# relayboard-v1.net
KiCad netlist of a schematic drawn in EAGLE
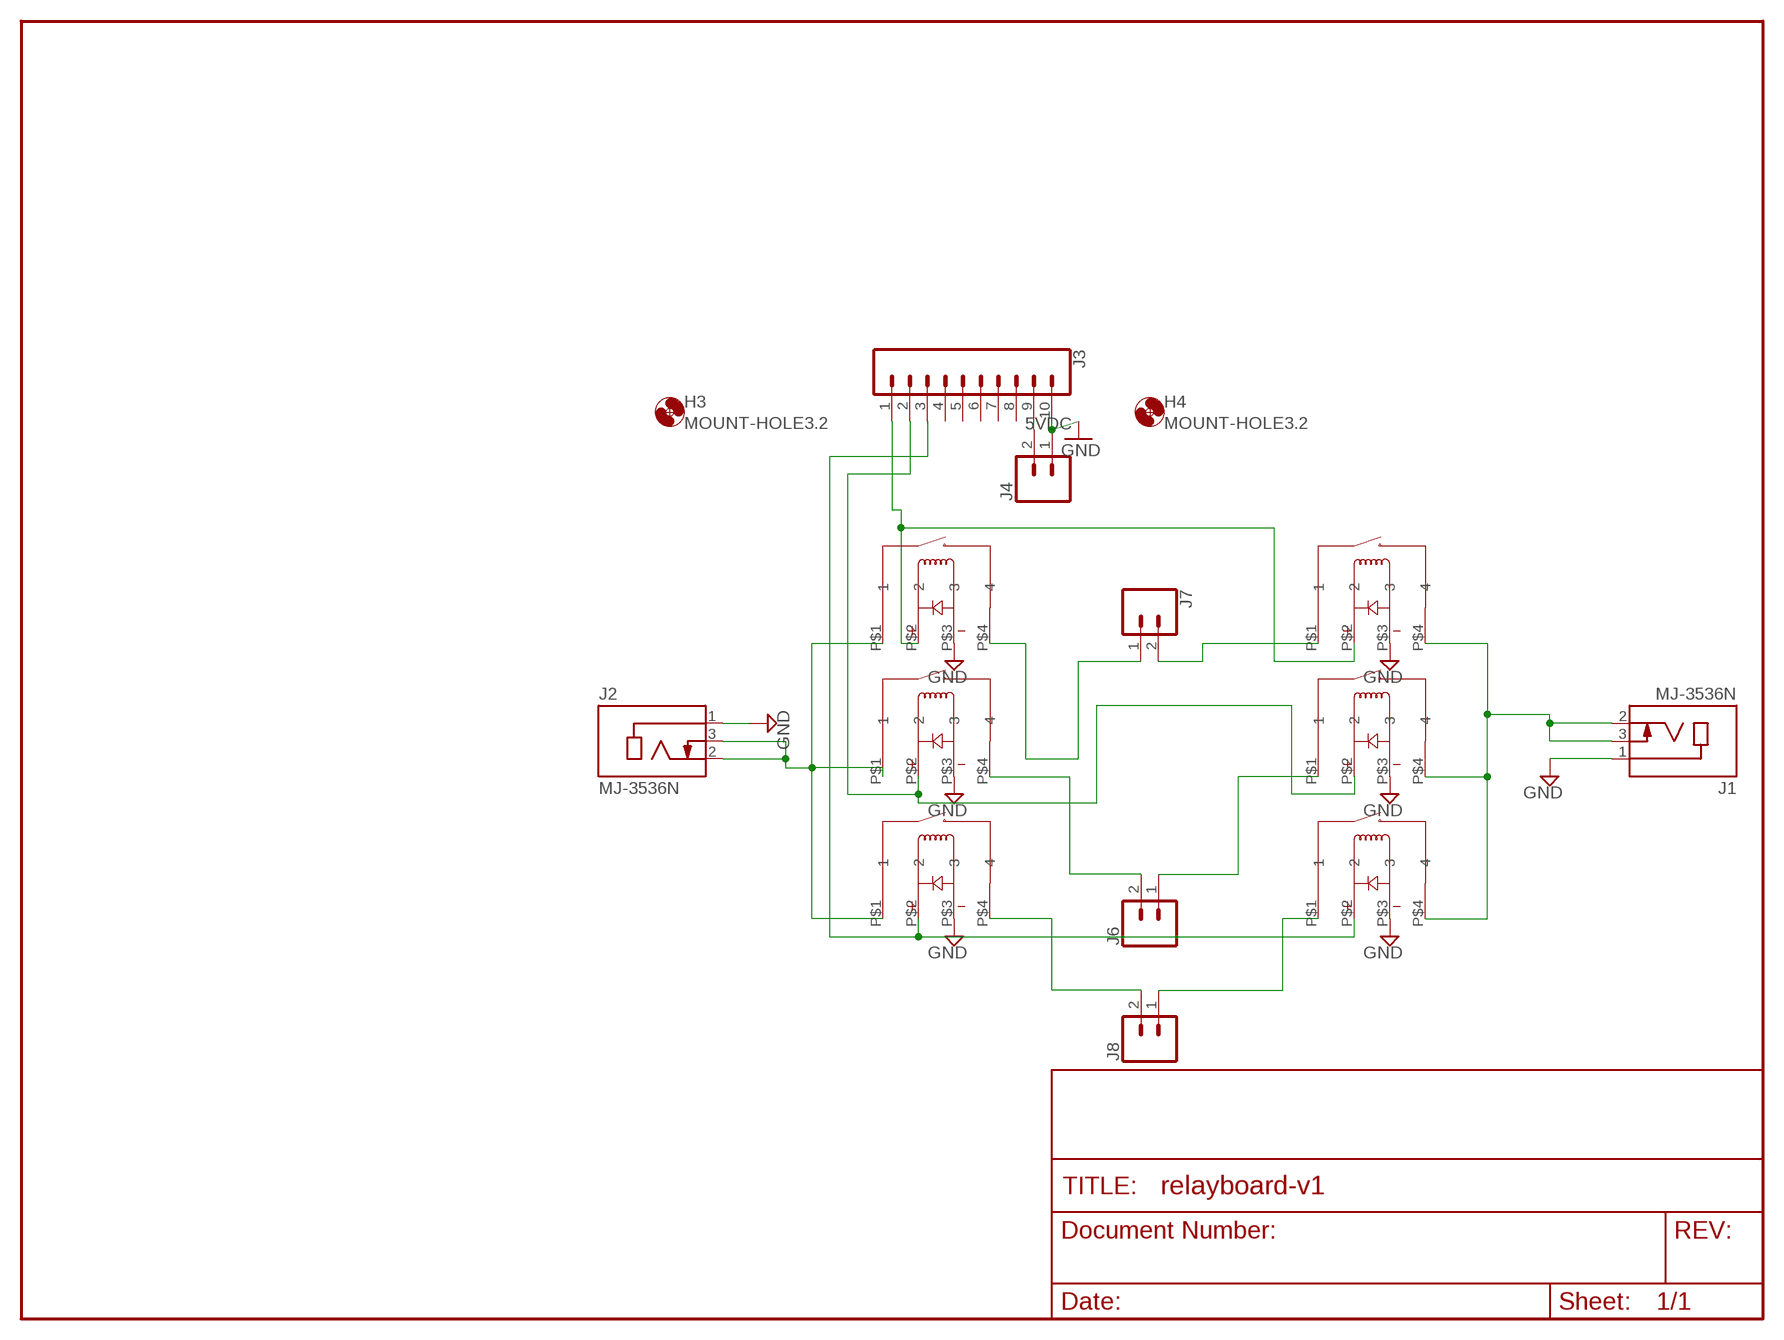
[diagram p0: schematic, sheet 1]

(export (version "E")
  (design (tool "Eeschema 10.0.6"))
  (components
    (comp (ref "H3")
      (value "MOUNT-HOLE3.2")
      (footprint "eagle-import:3,2")
      (libsource (lib "eagle-import") (part "MOUNT-HOLE3.2"))
    )
    (comp (ref "H4")
      (value "MOUNT-HOLE3.2")
      (footprint "eagle-import:3,2")
      (libsource (lib "eagle-import") (part "MOUNT-HOLE3.2"))
    )
    (comp (ref "J1")
      (value "MJ-3536N")
      (footprint "eagle-import:CUI_MJ-3536N")
      (fields (field (name "MANUFACTURER") "CUI INC"))
      (libsource (lib "eagle-import") (part "MJ-3536N"))
    )
    (comp (ref "J2")
      (value "MJ-3536N")
      (footprint "eagle-import:CUI_MJ-3536N")
      (fields (field (name "MANUFACTURER") "CUI INC"))
      (libsource (lib "eagle-import") (part "MJ-3536N"))
    )
    (comp (ref "J3")
      (value "CONN_10\"")
      (footprint "eagle-import:1X10")
      (libsource (lib "eagle-import") (part "CONN_10{dblquote}"))
    )
    (comp (ref "J4")
      (value "CONN_02")
      (footprint "eagle-import:1X02")
      (libsource (lib "eagle-import") (part "CONN_02"))
    )
    (comp (ref "J6")
      (value "CONN_02")
      (footprint "eagle-import:1X02")
      (libsource (lib "eagle-import") (part "CONN_02"))
    )
    (comp (ref "J7")
      (value "CONN_02")
      (footprint "eagle-import:1X02")
      (libsource (lib "eagle-import") (part "CONN_02"))
    )
    (comp (ref "J8")
      (value "CONN_02")
      (footprint "eagle-import:1X02")
      (libsource (lib "eagle-import") (part "CONN_02"))
    )
    (comp (ref "U$3")
      (value "RELAY-COMUS-3750-1331")
      (footprint "eagle-import:RELAY-COMUS-3570-1331")
      (libsource (lib "eagle-import") (part "RELAY-COMUS-3750-1331"))
    )
    (comp (ref "U$4")
      (value "RELAY-COMUS-3750-1331")
      (footprint "eagle-import:RELAY-COMUS-3570-1331")
      (libsource (lib "eagle-import") (part "RELAY-COMUS-3750-1331"))
    )
    (comp (ref "U$5")
      (value "RELAY-COMUS-3750-1331")
      (footprint "eagle-import:RELAY-COMUS-3570-1331")
      (libsource (lib "eagle-import") (part "RELAY-COMUS-3750-1331"))
    )
    (comp (ref "U$6")
      (value "RELAY-COMUS-3750-1331")
      (footprint "eagle-import:RELAY-COMUS-3570-1331")
      (libsource (lib "eagle-import") (part "RELAY-COMUS-3750-1331"))
    )
    (comp (ref "U$7")
      (value "RELAY-COMUS-3750-1331")
      (footprint "eagle-import:RELAY-COMUS-3570-1331")
      (libsource (lib "eagle-import") (part "RELAY-COMUS-3750-1331"))
    )
    (comp (ref "U$8")
      (value "RELAY-COMUS-3750-1331")
      (footprint "eagle-import:RELAY-COMUS-3570-1331")
      (libsource (lib "eagle-import") (part "RELAY-COMUS-3750-1331"))
    )
  )
  (nets
    (net (code "1") (name "/5VDC") (class "Default")
      (node (ref "J3") (pin "9") (pinfunction "9_9") (pintype "passive"))
      (node (ref "J4") (pin "2") (pinfunction "2_2") (pintype "passive"))
    )
    (net (code "2") (name "GND") (class "Default")
      (node (ref "J1") (pin "1") (pinfunction "1_1") (pintype "passive"))
      (node (ref "J2") (pin "1") (pinfunction "1_1") (pintype "passive"))
      (node (ref "J3") (pin "10") (pinfunction "10_10") (pintype "passive"))
      (node (ref "J4") (pin "1") (pinfunction "1_1") (pintype "passive"))
      (node (ref "U$3") (pin "P$3") (pinfunction "3_P$3") (pintype "bidirectional"))
      (node (ref "U$4") (pin "P$3") (pinfunction "3_P$3") (pintype "bidirectional"))
      (node (ref "U$5") (pin "P$3") (pinfunction "3_P$3") (pintype "bidirectional"))
      (node (ref "U$6") (pin "P$3") (pinfunction "3_P$3") (pintype "bidirectional"))
      (node (ref "U$7") (pin "P$3") (pinfunction "3_P$3") (pintype "bidirectional"))
      (node (ref "U$8") (pin "P$3") (pinfunction "3_P$3") (pintype "bidirectional"))
    )
    (net (code "3") (name "Net-(U$3-1)") (class "Default")
      (node (ref "J2") (pin "2") (pinfunction "2_2") (pintype "passive"))
      (node (ref "J2") (pin "3") (pinfunction "3_3") (pintype "passive"))
      (node (ref "U$3") (pin "P$1") (pinfunction "1_P$1") (pintype "bidirectional"))
      (node (ref "U$5") (pin "P$1") (pinfunction "1_P$1") (pintype "bidirectional"))
      (node (ref "U$7") (pin "P$1") (pinfunction "1_P$1") (pintype "bidirectional"))
    )
    (net (code "4") (name "Net-(U$3-2)") (class "Default")
      (node (ref "J3") (pin "1") (pinfunction "1_1") (pintype "passive"))
      (node (ref "U$3") (pin "P$2") (pinfunction "2_P$2") (pintype "bidirectional"))
      (node (ref "U$4") (pin "P$2") (pinfunction "2_P$2") (pintype "bidirectional"))
    )
    (net (code "5") (name "Net-(U$3-4)") (class "Default")
      (node (ref "J7") (pin "1") (pinfunction "1_1") (pintype "passive"))
      (node (ref "U$3") (pin "P$4") (pinfunction "4_P$4") (pintype "bidirectional"))
    )
    (net (code "6") (name "Net-(U$4-1)") (class "Default")
      (node (ref "J7") (pin "2") (pinfunction "2_2") (pintype "passive"))
      (node (ref "U$4") (pin "P$1") (pinfunction "1_P$1") (pintype "bidirectional"))
    )
    (net (code "7") (name "Net-(U$4-4)") (class "Default")
      (node (ref "J1") (pin "2") (pinfunction "2_2") (pintype "passive"))
      (node (ref "J1") (pin "3") (pinfunction "3_3") (pintype "passive"))
      (node (ref "U$4") (pin "P$4") (pinfunction "4_P$4") (pintype "bidirectional"))
      (node (ref "U$6") (pin "P$4") (pinfunction "4_P$4") (pintype "bidirectional"))
      (node (ref "U$8") (pin "P$4") (pinfunction "4_P$4") (pintype "bidirectional"))
    )
    (net (code "8") (name "Net-(U$5-2)") (class "Default")
      (node (ref "J3") (pin "2") (pinfunction "2_2") (pintype "passive"))
      (node (ref "U$5") (pin "P$2") (pinfunction "2_P$2") (pintype "bidirectional"))
      (node (ref "U$6") (pin "P$2") (pinfunction "2_P$2") (pintype "bidirectional"))
    )
    (net (code "9") (name "Net-(U$5-4)") (class "Default")
      (node (ref "J6") (pin "2") (pinfunction "2_2") (pintype "passive"))
      (node (ref "U$5") (pin "P$4") (pinfunction "4_P$4") (pintype "bidirectional"))
    )
    (net (code "10") (name "Net-(U$6-1)") (class "Default")
      (node (ref "J6") (pin "1") (pinfunction "1_1") (pintype "passive"))
      (node (ref "U$6") (pin "P$1") (pinfunction "1_P$1") (pintype "bidirectional"))
    )
    (net (code "11") (name "Net-(U$7-2)") (class "Default")
      (node (ref "J3") (pin "3") (pinfunction "3_3") (pintype "passive"))
      (node (ref "U$7") (pin "P$2") (pinfunction "2_P$2") (pintype "bidirectional"))
      (node (ref "U$8") (pin "P$2") (pinfunction "2_P$2") (pintype "bidirectional"))
    )
    (net (code "12") (name "Net-(U$7-4)") (class "Default")
      (node (ref "J8") (pin "2") (pinfunction "2_2") (pintype "passive"))
      (node (ref "U$7") (pin "P$4") (pinfunction "4_P$4") (pintype "bidirectional"))
    )
    (net (code "13") (name "Net-(U$8-1)") (class "Default")
      (node (ref "J8") (pin "1") (pinfunction "1_1") (pintype "passive"))
      (node (ref "U$8") (pin "P$1") (pinfunction "1_P$1") (pintype "bidirectional"))
    )
    (net (code "14") (name "unconnected-(J3-Pad4)") (class "Default")
      (node (ref "J3") (pin "4") (pinfunction "4_4") (pintype "passive"))
    )
    (net (code "15") (name "unconnected-(J3-Pad5)") (class "Default")
      (node (ref "J3") (pin "5") (pinfunction "5_5") (pintype "passive"))
    )
    (net (code "16") (name "unconnected-(J3-Pad6)") (class "Default")
      (node (ref "J3") (pin "6") (pinfunction "6_6") (pintype "passive"))
    )
    (net (code "17") (name "unconnected-(J3-Pad7)") (class "Default")
      (node (ref "J3") (pin "7") (pinfunction "7_7") (pintype "passive"))
    )
    (net (code "18") (name "unconnected-(J3-Pad8)") (class "Default")
      (node (ref "J3") (pin "8") (pinfunction "8_8") (pintype "passive"))
    )
  )
)
